# TUEV06.net
KiCad netlist of a schematic drawn in EAGLE
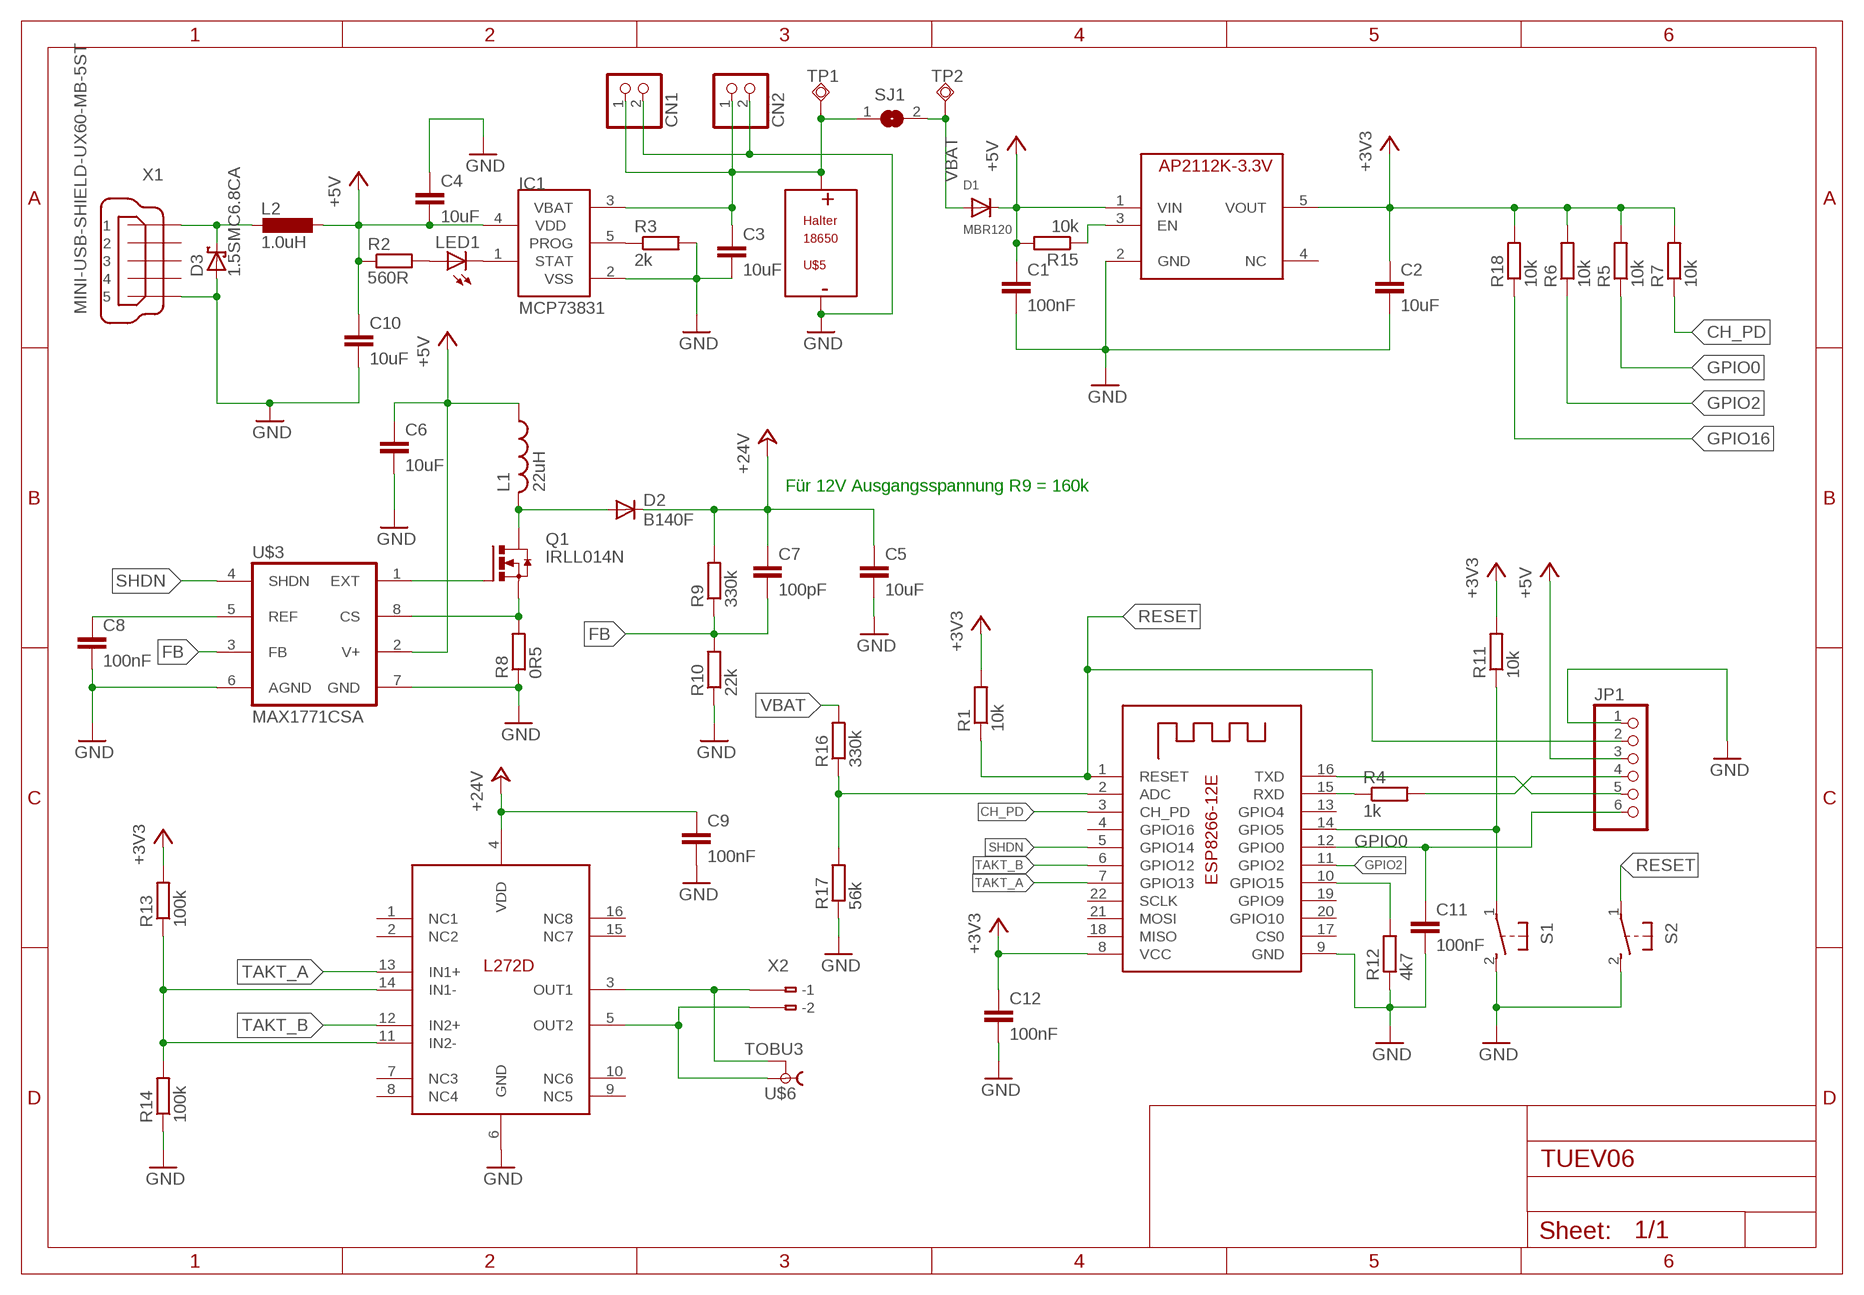
[diagram p0: schematic, sheet 1]

(export (version "E")
  (design (tool "Eeschema 10.0.6"))
  (components
    (comp (ref "C1")
      (value "100nF")
      (footprint "eagle-import:C0603K")
      (libsource (lib "eagle-import") (part "C-EUC0603K"))
    )
    (comp (ref "C2")
      (value "10uF")
      (footprint "eagle-import:C0603K")
      (libsource (lib "eagle-import") (part "C-EUC0603K"))
    )
    (comp (ref "C3")
      (value "10uF")
      (footprint "eagle-import:C0603K")
      (libsource (lib "eagle-import") (part "C-EUC0603K"))
    )
    (comp (ref "C4")
      (value "10uF")
      (footprint "eagle-import:C0603K")
      (libsource (lib "eagle-import") (part "C-EUC0603K"))
    )
    (comp (ref "C5")
      (value "10uF")
      (footprint "eagle-import:C1210K")
      (libsource (lib "eagle-import") (part "C-EUC1210K"))
    )
    (comp (ref "C6")
      (value "10uF")
      (footprint "eagle-import:C0603K")
      (libsource (lib "eagle-import") (part "C-EUC0603K"))
    )
    (comp (ref "C7")
      (value "100pF")
      (footprint "eagle-import:C1206")
      (libsource (lib "eagle-import") (part "C-EUC1206"))
    )
    (comp (ref "C8")
      (value "100nF")
      (footprint "eagle-import:C0603K")
      (libsource (lib "eagle-import") (part "C-EUC0603K"))
    )
    (comp (ref "C9")
      (value "100nF")
      (footprint "eagle-import:C0603K")
      (libsource (lib "eagle-import") (part "C-EUC0603K"))
    )
    (comp (ref "C10")
      (value "10uF")
      (footprint "eagle-import:C0603K")
      (libsource (lib "eagle-import") (part "C-EUC0603K"))
    )
    (comp (ref "C11")
      (value "100nF")
      (footprint "eagle-import:C0603K")
      (libsource (lib "eagle-import") (part "C-EUC0603K"))
    )
    (comp (ref "C12")
      (value "100nF")
      (footprint "eagle-import:C0603K")
      (libsource (lib "eagle-import") (part "C-EUC0603K"))
    )
    (comp (ref "CN1")
      (value "JST_2PIN-SMT-RA")
      (footprint "eagle-import:JST-PH-2-SMT-RA")
      (libsource (lib "eagle-import") (part "JST_2PIN-SMT-RA"))
    )
    (comp (ref "CN2")
      (value "JST_2PIN-SMT-RA")
      (footprint "eagle-import:JST-PH-2-SMT-RA")
      (libsource (lib "eagle-import") (part "JST_2PIN-SMT-RA"))
    )
    (comp (ref "D1")
      (value "MBR120")
      (footprint "eagle-import:SOD-123")
      (libsource (lib "eagle-import") (part "DIODESOD-123"))
    )
    (comp (ref "D2")
      (value "B140F")
      (footprint "eagle-import:DO214AC")
      (libsource (lib "eagle-import") (part "DIODE-DO214AC"))
    )
    (comp (ref "D3")
      (value "1.5SMC6.8CA")
      (footprint "eagle-import:SMC")
      (libsource (lib "eagle-import") (part "SCHOTTKY-DIODESMC"))
    )
    (comp (ref "IC1")
      (value "MCP73831")
      (footprint "eagle-import:SOT23-5L")
      (libsource (lib "eagle-import") (part "MCP73831"))
    )
    (comp (ref "JP1")
      (value "PINHD-1X6")
      (footprint "eagle-import:1X06")
      (libsource (lib "eagle-import") (part "PINHD-1X6"))
    )
    (comp (ref "L1")
      (value "22uH")
      (footprint "eagle-import:L5650M")
      (libsource (lib "eagle-import") (part "L-USL5650M"))
    )
    (comp (ref "L2")
      (value "1.0uH")
      (footprint "eagle-import:L3230M")
      (libsource (lib "eagle-import") (part "L-EUL3230M"))
    )
    (comp (ref "LED1")
      (value "LEDCHIPLED_0805")
      (footprint "eagle-import:CHIPLED_0805")
      (libsource (lib "eagle-import") (part "LEDCHIPLED_0805"))
    )
    (comp (ref "Q1")
      (value "IRLL014N")
      (footprint "eagle-import:SOT223")
      (libsource (lib "eagle-import") (part "N-HEXFET-2D_?-SOT232IRLL014N"))
    )
    (comp (ref "R1")
      (value "10k")
      (footprint "eagle-import:M1206")
      (libsource (lib "eagle-import") (part "R-EU_M1206"))
    )
    (comp (ref "R2")
      (value "560R")
      (footprint "eagle-import:M1206")
      (libsource (lib "eagle-import") (part "R-EU_M1206"))
    )
    (comp (ref "R3")
      (value "2k")
      (footprint "eagle-import:M1206")
      (libsource (lib "eagle-import") (part "R-EU_M1206"))
    )
    (comp (ref "R4")
      (value "1k")
      (footprint "eagle-import:M1206")
      (libsource (lib "eagle-import") (part "R-EU_M1206"))
    )
    (comp (ref "R5")
      (value "10k")
      (footprint "eagle-import:M1206")
      (libsource (lib "eagle-import") (part "R-EU_M1206"))
    )
    (comp (ref "R6")
      (value "10k")
      (footprint "eagle-import:M1206")
      (libsource (lib "eagle-import") (part "R-EU_M1206"))
    )
    (comp (ref "R7")
      (value "10k")
      (footprint "eagle-import:M1206")
      (libsource (lib "eagle-import") (part "R-EU_M1206"))
    )
    (comp (ref "R8")
      (value "0R5")
      (footprint "eagle-import:R2512")
      (libsource (lib "eagle-import") (part "R-EU_R2512"))
    )
    (comp (ref "R9")
      (value "330k")
      (footprint "eagle-import:M1206")
      (libsource (lib "eagle-import") (part "R-EU_M1206"))
    )
    (comp (ref "R10")
      (value "22k")
      (footprint "eagle-import:M1206")
      (libsource (lib "eagle-import") (part "R-EU_M1206"))
    )
    (comp (ref "R11")
      (value "10k")
      (footprint "eagle-import:M1206")
      (libsource (lib "eagle-import") (part "R-EU_M1206"))
    )
    (comp (ref "R12")
      (value "4k7")
      (footprint "eagle-import:M1206")
      (libsource (lib "eagle-import") (part "R-EU_M1206"))
    )
    (comp (ref "R13")
      (value "100k")
      (footprint "eagle-import:M1206")
      (libsource (lib "eagle-import") (part "R-EU_M1206"))
    )
    (comp (ref "R14")
      (value "100k")
      (footprint "eagle-import:M1206")
      (libsource (lib "eagle-import") (part "R-EU_M1206"))
    )
    (comp (ref "R15")
      (value "10k")
      (footprint "eagle-import:M1206")
      (libsource (lib "eagle-import") (part "R-EU_M1206"))
    )
    (comp (ref "R16")
      (value "330k")
      (footprint "eagle-import:M1206")
      (libsource (lib "eagle-import") (part "R-EU_M1206"))
    )
    (comp (ref "R17")
      (value "56k")
      (footprint "eagle-import:M1206")
      (libsource (lib "eagle-import") (part "R-EU_M1206"))
    )
    (comp (ref "R18")
      (value "10k")
      (footprint "eagle-import:M1206")
      (libsource (lib "eagle-import") (part "R-EU_M1206"))
    )
    (comp (ref "S1")
      (value "31-XX")
      (footprint "eagle-import:B3F-31XX")
      (fields (field (name "MPN") "B3F-3100"))
      (libsource (lib "eagle-import") (part "31-XX"))
    )
    (comp (ref "S2")
      (value "31-XX")
      (footprint "eagle-import:B3F-31XX")
      (fields (field (name "MPN") "B3F-3100"))
      (libsource (lib "eagle-import") (part "31-XX"))
    )
    (comp (ref "SJ1") (value "SJ") (footprint "eagle-import:SJ") (libsource (lib "eagle-import") (part "SJ")))
    (comp (ref "TP1")
      (value "TPSQPAD1-13Y")
      (footprint "eagle-import:P1-13Y")
      (libsource (lib "eagle-import") (part "TPSQPAD1-13Y"))
    )
    (comp (ref "TP2")
      (value "TPSQPAD1-13Y")
      (footprint "eagle-import:P1-13Y")
      (libsource (lib "eagle-import") (part "TPSQPAD1-13Y"))
    )
    (comp (ref "U$1")
      (value "AP2112-3.3")
      (footprint "eagle-import:SOT23-5L")
      (libsource (lib "eagle-import") (part "AP2112-3.3"))
    )
    (comp (ref "U$2")
      (value "L272D")
      (footprint "eagle-import:SO16")
      (libsource (lib "eagle-import") (part "L272D"))
    )
    (comp (ref "U$3")
      (value "MAX1771CSA")
      (footprint "eagle-import:SO08")
      (libsource (lib "eagle-import") (part "MAX1771CSA"))
    )
    (comp (ref "U$4")
      (value "ESP-12E")
      (footprint "eagle-import:ESP-12E")
      (libsource (lib "eagle-import") (part "ESP-12E"))
    )
    (comp (ref "U$5")
      (value "HA1X18650SMD")
      (footprint "eagle-import:HA1X18650SMD")
      (libsource (lib "eagle-import") (part "HA1X18650SMD"))
    )
    (comp (ref "U$6")
      (value "TOBU3")
      (footprint "eagle-import:TOBU3-REICHELT")
      (libsource (lib "eagle-import") (part "TOBU3-REICHELT"))
    )
    (comp (ref "X1")
      (value "MINI-USB-SHIELD-UX60-MB-5ST")
      (footprint "eagle-import:UX60-MB-5ST")
      (libsource (lib "eagle-import") (part "MINI-USB-SHIELD-UX60-MB-5ST"))
    )
    (comp (ref "X2")
      (value "233-102")
      (footprint "eagle-import:233-102")
      (libsource (lib "eagle-import") (part "233-102"))
    )
  )
  (nets
    (net (code "1") (name "+3V3") (class "Default")
      (node (ref "C12") (pin "1") (pinfunction "1_1") (pintype "passive"))
      (node (ref "C2") (pin "1") (pinfunction "1_1") (pintype "passive"))
      (node (ref "R1") (pin "2") (pinfunction "2_2") (pintype "passive"))
      (node (ref "R11") (pin "2") (pinfunction "2_2") (pintype "passive"))
      (node (ref "R13") (pin "2") (pinfunction "2_2") (pintype "passive"))
      (node (ref "R18") (pin "2") (pinfunction "2_2") (pintype "passive"))
      (node (ref "R5") (pin "2") (pinfunction "2_2") (pintype "passive"))
      (node (ref "R6") (pin "2") (pinfunction "2_2") (pintype "passive"))
      (node (ref "R7") (pin "2") (pinfunction "2_2") (pintype "passive"))
      (node (ref "U$1") (pin "5") (pinfunction "VOUT_5") (pintype "power_in"))
      (node (ref "U$4") (pin "8") (pinfunction "VCC_8") (pintype "power_in"))
    )
    (net (code "2") (name "+5V") (class "Default")
      (node (ref "C1") (pin "1") (pinfunction "1_1") (pintype "passive"))
      (node (ref "C10") (pin "1") (pinfunction "1_1") (pintype "passive"))
      (node (ref "C4") (pin "2") (pinfunction "2_2") (pintype "passive"))
      (node (ref "C6") (pin "1") (pinfunction "1_1") (pintype "passive"))
      (node (ref "D1") (pin "C") (pinfunction "C_C") (pintype "passive"))
      (node (ref "IC1") (pin "4") (pinfunction "VDD_4") (pintype "bidirectional"))
      (node (ref "JP1") (pin "3") (pinfunction "3_3") (pintype "passive"))
      (node (ref "L1") (pin "1") (pinfunction "1_1") (pintype "passive"))
      (node (ref "L2") (pin "1") (pinfunction "1_1") (pintype "passive"))
      (node (ref "R15") (pin "2") (pinfunction "2_2") (pintype "passive"))
      (node (ref "R2") (pin "1") (pinfunction "1_1") (pintype "passive"))
      (node (ref "U$1") (pin "1") (pinfunction "VIN_1") (pintype "power_in"))
      (node (ref "U$3") (pin "2") (pinfunction "V+_2") (pintype "power_in"))
    )
    (net (code "3") (name "+24V") (class "Default")
      (node (ref "C5") (pin "1") (pinfunction "1_1") (pintype "passive"))
      (node (ref "C7") (pin "1") (pinfunction "1_1") (pintype "passive"))
      (node (ref "C9") (pin "1") (pinfunction "1_1") (pintype "passive"))
      (node (ref "D2") (pin "C") (pinfunction "C_C") (pintype "passive"))
      (node (ref "R9") (pin "2") (pinfunction "2_2") (pintype "passive"))
      (node (ref "U$2") (pin "4") (pinfunction "VDD_4") (pintype "power_in"))
    )
    (net (code "4") (name "CH_PD") (class "Default")
      (node (ref "R7") (pin "1") (pinfunction "1_1") (pintype "passive"))
      (node (ref "U$4") (pin "3") (pinfunction "CH_PD_3") (pintype "input"))
    )
    (net (code "5") (name "FB") (class "Default")
      (node (ref "C7") (pin "2") (pinfunction "2_2") (pintype "passive"))
      (node (ref "R10") (pin "2") (pinfunction "2_2") (pintype "passive"))
      (node (ref "R9") (pin "1") (pinfunction "1_1") (pintype "passive"))
      (node (ref "U$3") (pin "3") (pinfunction "FB_3") (pintype "input"))
    )
    (net (code "6") (name "GND") (class "Default")
      (node (ref "C1") (pin "2") (pinfunction "2_2") (pintype "passive"))
      (node (ref "C10") (pin "2") (pinfunction "2_2") (pintype "passive"))
      (node (ref "C11") (pin "2") (pinfunction "2_2") (pintype "passive"))
      (node (ref "C12") (pin "2") (pinfunction "2_2") (pintype "passive"))
      (node (ref "C2") (pin "2") (pinfunction "2_2") (pintype "passive"))
      (node (ref "C3") (pin "2") (pinfunction "2_2") (pintype "passive"))
      (node (ref "C4") (pin "1") (pinfunction "1_1") (pintype "passive"))
      (node (ref "C5") (pin "2") (pinfunction "2_2") (pintype "passive"))
      (node (ref "C6") (pin "2") (pinfunction "2_2") (pintype "passive"))
      (node (ref "C8") (pin "2") (pinfunction "2_2") (pintype "passive"))
      (node (ref "C9") (pin "2") (pinfunction "2_2") (pintype "passive"))
      (node (ref "CN1") (pin "2") (pinfunction "1_2") (pintype "passive"))
      (node (ref "CN2") (pin "2") (pinfunction "1_2") (pintype "passive"))
      (node (ref "D3") (pin "A") (pinfunction "A_A") (pintype "passive"))
      (node (ref "IC1") (pin "2") (pinfunction "VSS_2") (pintype "bidirectional"))
      (node (ref "JP1") (pin "1") (pinfunction "1_1") (pintype "passive"))
      (node (ref "R10") (pin "1") (pinfunction "1_1") (pintype "passive"))
      (node (ref "R12") (pin "1") (pinfunction "1_1") (pintype "passive"))
      (node (ref "R14") (pin "1") (pinfunction "1_1") (pintype "passive"))
      (node (ref "R17") (pin "1") (pinfunction "1_1") (pintype "passive"))
      (node (ref "R3") (pin "2") (pinfunction "2_2") (pintype "passive"))
      (node (ref "R8") (pin "1") (pinfunction "1_1") (pintype "passive"))
      (node (ref "S1") (pin "2") (pinfunction "S_2") (pintype "passive"))
      (node (ref "S2") (pin "2") (pinfunction "S_2") (pintype "passive"))
      (node (ref "U$1") (pin "2") (pinfunction "GND_2") (pintype "power_in"))
      (node (ref "U$2") (pin "6") (pinfunction "GND_6") (pintype "power_in"))
      (node (ref "U$3") (pin "6") (pinfunction "AGND_6") (pintype "input"))
      (node (ref "U$3") (pin "7") (pinfunction "GND_7") (pintype "power_in"))
      (node (ref "U$4") (pin "9") (pinfunction "GND_9") (pintype "power_in"))
      (node (ref "U$5") (pin "P$2-") (pinfunction "P$2-_P$2-") (pintype "bidirectional"))
      (node (ref "X1") (pin "5") (pinfunction "5_5") (pintype "input"))
    )
    (net (code "7") (name "GPIO0") (class "Default")
      (node (ref "C11") (pin "1") (pinfunction "1_1") (pintype "passive"))
      (node (ref "JP1") (pin "6") (pinfunction "6_6") (pintype "passive"))
      (node (ref "R5") (pin "1") (pinfunction "1_1") (pintype "passive"))
      (node (ref "U$4") (pin "12") (pinfunction "GPIO0_12") (pintype "bidirectional"))
    )
    (net (code "8") (name "GPIO2") (class "Default")
      (node (ref "R6") (pin "1") (pinfunction "1_1") (pintype "passive"))
      (node (ref "U$4") (pin "11") (pinfunction "GPIO2_11") (pintype "bidirectional"))
    )
    (net (code "9") (name "GPIO16") (class "Default")
      (node (ref "R18") (pin "1") (pinfunction "1_1") (pintype "passive"))
    )
    (net (code "10") (name "Net-(CN1-2)") (class "Default")
      (node (ref "C3") (pin "1") (pinfunction "1_1") (pintype "passive"))
      (node (ref "CN1") (pin "1") (pinfunction "2_1") (pintype "passive"))
      (node (ref "CN2") (pin "1") (pinfunction "2_1") (pintype "passive"))
      (node (ref "IC1") (pin "3") (pinfunction "VBAT_3") (pintype "bidirectional"))
      (node (ref "SJ1") (pin "1") (pinfunction "1_1") (pintype "passive"))
      (node (ref "TP1") (pin "TP") (pinfunction "TP_TP") (pintype "input"))
      (node (ref "U$5") (pin "P$1+") (pinfunction "P$1+_P$1+") (pintype "bidirectional"))
    )
    (net (code "11") (name "Net-(D2-PadA)") (class "Default")
      (node (ref "D2") (pin "A") (pinfunction "A_A") (pintype "passive"))
      (node (ref "L1") (pin "2") (pinfunction "2_2") (pintype "passive"))
      (node (ref "Q1") (pin "2") (pinfunction "D_2") (pintype "passive"))
      (node (ref "Q1") (pin "4") (pinfunction "D_4") (pintype "passive"))
    )
    (net (code "12") (name "Net-(D3-PadC)") (class "Default")
      (node (ref "D3") (pin "C") (pinfunction "C_C") (pintype "passive"))
      (node (ref "L2") (pin "2") (pinfunction "2_2") (pintype "passive"))
      (node (ref "X1") (pin "1") (pinfunction "1_1") (pintype "input"))
    )
    (net (code "13") (name "Net-(IC1-PROG)") (class "Default")
      (node (ref "IC1") (pin "5") (pinfunction "PROG_5") (pintype "bidirectional"))
      (node (ref "R3") (pin "1") (pinfunction "1_1") (pintype "passive"))
    )
    (net (code "14") (name "Net-(IC1-STAT)") (class "Default")
      (node (ref "IC1") (pin "1") (pinfunction "STAT_1") (pintype "bidirectional"))
      (node (ref "LED1") (pin "C") (pinfunction "C_C") (pintype "passive"))
    )
    (net (code "15") (name "Net-(JP1-Pad4)") (class "Default")
      (node (ref "JP1") (pin "4") (pinfunction "4_4") (pintype "passive"))
      (node (ref "R4") (pin "2") (pinfunction "2_2") (pintype "passive"))
    )
    (net (code "16") (name "Net-(LED1-PadA)") (class "Default")
      (node (ref "LED1") (pin "A") (pinfunction "A_A") (pintype "passive"))
      (node (ref "R2") (pin "2") (pinfunction "2_2") (pintype "passive"))
    )
    (net (code "17") (name "Net-(Q1-G)") (class "Default")
      (node (ref "Q1") (pin "1") (pinfunction "G_1") (pintype "passive"))
      (node (ref "U$3") (pin "1") (pinfunction "EXT_1") (pintype "output"))
    )
    (net (code "18") (name "Net-(Q1-S)") (class "Default")
      (node (ref "Q1") (pin "3") (pinfunction "S_3") (pintype "passive"))
      (node (ref "R8") (pin "2") (pinfunction "2_2") (pintype "passive"))
      (node (ref "U$3") (pin "8") (pinfunction "CS_8") (pintype "input"))
    )
    (net (code "19") (name "Net-(S1-P)") (class "Default")
      (node (ref "R11") (pin "1") (pinfunction "1_1") (pintype "passive"))
      (node (ref "S1") (pin "1") (pinfunction "P_1") (pintype "passive"))
      (node (ref "U$4") (pin "14") (pinfunction "GPIO5_14") (pintype "bidirectional"))
    )
    (net (code "20") (name "Net-(U$1-EN)") (class "Default")
      (node (ref "R15") (pin "1") (pinfunction "1_1") (pintype "passive"))
      (node (ref "U$1") (pin "3") (pinfunction "EN_3") (pintype "input"))
    )
    (net (code "21") (name "Net-(U$2-IN1-)") (class "Default")
      (node (ref "R13") (pin "1") (pinfunction "1_1") (pintype "passive"))
      (node (ref "R14") (pin "2") (pinfunction "2_2") (pintype "passive"))
      (node (ref "U$2") (pin "11") (pinfunction "IN2-_11") (pintype "bidirectional"))
      (node (ref "U$2") (pin "14") (pinfunction "IN1-_14") (pintype "bidirectional"))
    )
    (net (code "22") (name "Net-(U$2-OUT1)") (class "Default")
      (node (ref "U$2") (pin "3") (pinfunction "OUT1_3") (pintype "output"))
      (node (ref "U$6") (pin "2") (pinfunction "2_2") (pintype "passive"))
      (node (ref "U$6") (pin "2@1") (pinfunction "2_2@1") (pintype "passive"))
      (node (ref "U$6") (pin "2@2") (pinfunction "2_2@2") (pintype "passive"))
      (node (ref "X2") (pin "B1") (pinfunction "B-1_B1") (pintype "passive"))
    )
    (net (code "23") (name "Net-(U$2-OUT2)") (class "Default")
      (node (ref "U$2") (pin "5") (pinfunction "OUT2_5") (pintype "output"))
      (node (ref "U$6") (pin "1") (pinfunction "1_1") (pintype "passive"))
      (node (ref "X2") (pin "B2") (pinfunction "B-2_B2") (pintype "passive"))
    )
    (net (code "24") (name "Net-(U$3-REF)") (class "Default")
      (node (ref "C8") (pin "1") (pinfunction "1_1") (pintype "passive"))
      (node (ref "U$3") (pin "5") (pinfunction "REF_5") (pintype "input"))
    )
    (net (code "25") (name "Net-(U$4-ADC)") (class "Default")
      (node (ref "R16") (pin "1") (pinfunction "1_1") (pintype "passive"))
      (node (ref "R17") (pin "2") (pinfunction "2_2") (pintype "passive"))
      (node (ref "U$4") (pin "2") (pinfunction "ADC_2") (pintype "passive"))
    )
    (net (code "26") (name "Net-(U$4-GPIO15)") (class "Default")
      (node (ref "R12") (pin "2") (pinfunction "2_2") (pintype "passive"))
      (node (ref "U$4") (pin "10") (pinfunction "GPIO15_10") (pintype "bidirectional"))
    )
    (net (code "27") (name "Net-(U$4-RXD)") (class "Default")
      (node (ref "R4") (pin "1") (pinfunction "1_1") (pintype "passive"))
      (node (ref "U$4") (pin "15") (pinfunction "RXD_15") (pintype "input"))
    )
    (net (code "28") (name "Net-(U$4-TXD)") (class "Default")
      (node (ref "JP1") (pin "5") (pinfunction "5_5") (pintype "passive"))
      (node (ref "U$4") (pin "16") (pinfunction "TXD_16") (pintype "output"))
    )
    (net (code "29") (name "RESET") (class "Default")
      (node (ref "JP1") (pin "2") (pinfunction "2_2") (pintype "passive"))
      (node (ref "R1") (pin "1") (pinfunction "1_1") (pintype "passive"))
      (node (ref "S2") (pin "1") (pinfunction "P_1") (pintype "passive"))
      (node (ref "U$4") (pin "1") (pinfunction "RESET_1") (pintype "input"))
    )
    (net (code "30") (name "SHDN") (class "Default")
      (node (ref "U$3") (pin "4") (pinfunction "SHDN_4") (pintype "input"))
      (node (ref "U$4") (pin "5") (pinfunction "GPIO14_5") (pintype "bidirectional"))
    )
    (net (code "31") (name "TAKT_A") (class "Default")
      (node (ref "U$2") (pin "13") (pinfunction "IN1+_13") (pintype "input"))
      (node (ref "U$4") (pin "7") (pinfunction "GPIO13_7") (pintype "bidirectional"))
    )
    (net (code "32") (name "TAKT_B") (class "Default")
      (node (ref "U$2") (pin "12") (pinfunction "IN2+_12") (pintype "bidirectional"))
      (node (ref "U$4") (pin "6") (pinfunction "GPIO12_6") (pintype "bidirectional"))
    )
    (net (code "33") (name "VBAT") (class "Default")
      (node (ref "D1") (pin "A") (pinfunction "A_A") (pintype "passive"))
      (node (ref "R16") (pin "2") (pinfunction "2_2") (pintype "passive"))
      (node (ref "SJ1") (pin "2") (pinfunction "2_2") (pintype "passive"))
      (node (ref "TP2") (pin "TP") (pinfunction "TP_TP") (pintype "input"))
    )
    (net (code "34") (name "unconnected-(U$1-NC-Pad4)") (class "Default")
      (node (ref "U$1") (pin "4") (pinfunction "NC_4") (pintype "no_connect"))
    )
    (net (code "35") (name "unconnected-(U$2-NC1-Pad1)") (class "Default")
      (node (ref "U$2") (pin "1") (pinfunction "NC1_1") (pintype "no_connect"))
    )
    (net (code "36") (name "unconnected-(U$2-NC2-Pad2)") (class "Default")
      (node (ref "U$2") (pin "2") (pinfunction "NC2_2") (pintype "bidirectional"))
    )
    (net (code "37") (name "unconnected-(U$2-NC3-Pad7)") (class "Default")
      (node (ref "U$2") (pin "7") (pinfunction "NC3_7") (pintype "bidirectional"))
    )
    (net (code "38") (name "unconnected-(U$2-NC4-Pad8)") (class "Default")
      (node (ref "U$2") (pin "8") (pinfunction "NC4_8") (pintype "bidirectional"))
    )
    (net (code "39") (name "unconnected-(U$2-NC5-Pad9)") (class "Default")
      (node (ref "U$2") (pin "9") (pinfunction "NC5_9") (pintype "bidirectional"))
    )
    (net (code "40") (name "unconnected-(U$2-NC6-Pad10)") (class "Default")
      (node (ref "U$2") (pin "10") (pinfunction "NC6_10") (pintype "bidirectional"))
    )
    (net (code "41") (name "unconnected-(U$2-NC7-Pad15)") (class "Default")
      (node (ref "U$2") (pin "15") (pinfunction "NC7_15") (pintype "bidirectional"))
    )
    (net (code "42") (name "unconnected-(U$2-NC8-Pad16)") (class "Default")
      (node (ref "U$2") (pin "16") (pinfunction "NC8_16") (pintype "bidirectional"))
    )
    (net (code "43") (name "unconnected-(U$4-CS0-Pad17)") (class "Default")
      (node (ref "U$4") (pin "17") (pinfunction "CS0_17") (pintype "bidirectional"))
    )
    (net (code "44") (name "unconnected-(U$4-GPIO4-Pad13)") (class "Default")
      (node (ref "U$4") (pin "13") (pinfunction "GPIO4_13") (pintype "bidirectional"))
    )
    (net (code "45") (name "unconnected-(U$4-GPIO9-Pad19)") (class "Default")
      (node (ref "U$4") (pin "19") (pinfunction "GPIO9_19") (pintype "bidirectional"))
    )
    (net (code "46") (name "unconnected-(U$4-GPIO10-Pad20)") (class "Default")
      (node (ref "U$4") (pin "20") (pinfunction "GPIO10_20") (pintype "bidirectional"))
    )
    (net (code "47") (name "unconnected-(U$4-GPIO16-Pad4)") (class "Default")
      (node (ref "U$4") (pin "4") (pinfunction "GPIO16_4") (pintype "bidirectional"))
    )
    (net (code "48") (name "unconnected-(U$4-MISO-Pad18)") (class "Default")
      (node (ref "U$4") (pin "18") (pinfunction "MISO_18") (pintype "bidirectional"))
    )
    (net (code "49") (name "unconnected-(U$4-MOSI-Pad21)") (class "Default")
      (node (ref "U$4") (pin "21") (pinfunction "MOSI_21") (pintype "bidirectional"))
    )
    (net (code "50") (name "unconnected-(U$4-SCLK-Pad22)") (class "Default")
      (node (ref "U$4") (pin "22") (pinfunction "SCLK_22") (pintype "bidirectional"))
    )
    (net (code "51") (name "unconnected-(X1-Pad2)") (class "Default")
      (node (ref "X1") (pin "2") (pinfunction "2_2") (pintype "input"))
    )
    (net (code "52") (name "unconnected-(X1-Pad3)") (class "Default")
      (node (ref "X1") (pin "3") (pinfunction "3_3") (pintype "input"))
    )
    (net (code "53") (name "unconnected-(X1-Pad4)") (class "Default")
      (node (ref "X1") (pin "4") (pinfunction "4_4") (pintype "input"))
    )
    (net (code "54") (name "unconnected-(X2--1-PadA1)") (class "Default")
      (node (ref "X2") (pin "A1") (pinfunction "-1_A1") (pintype "passive"))
    )
    (net (code "55") (name "unconnected-(X2--2-PadA2)") (class "Default")
      (node (ref "X2") (pin "A2") (pinfunction "-2_A2") (pintype "passive"))
    )
  )
)
